# S7DG2_MCU_only_edge_Power_SPI.net
KiCad netlist of a schematic drawn in EAGLE
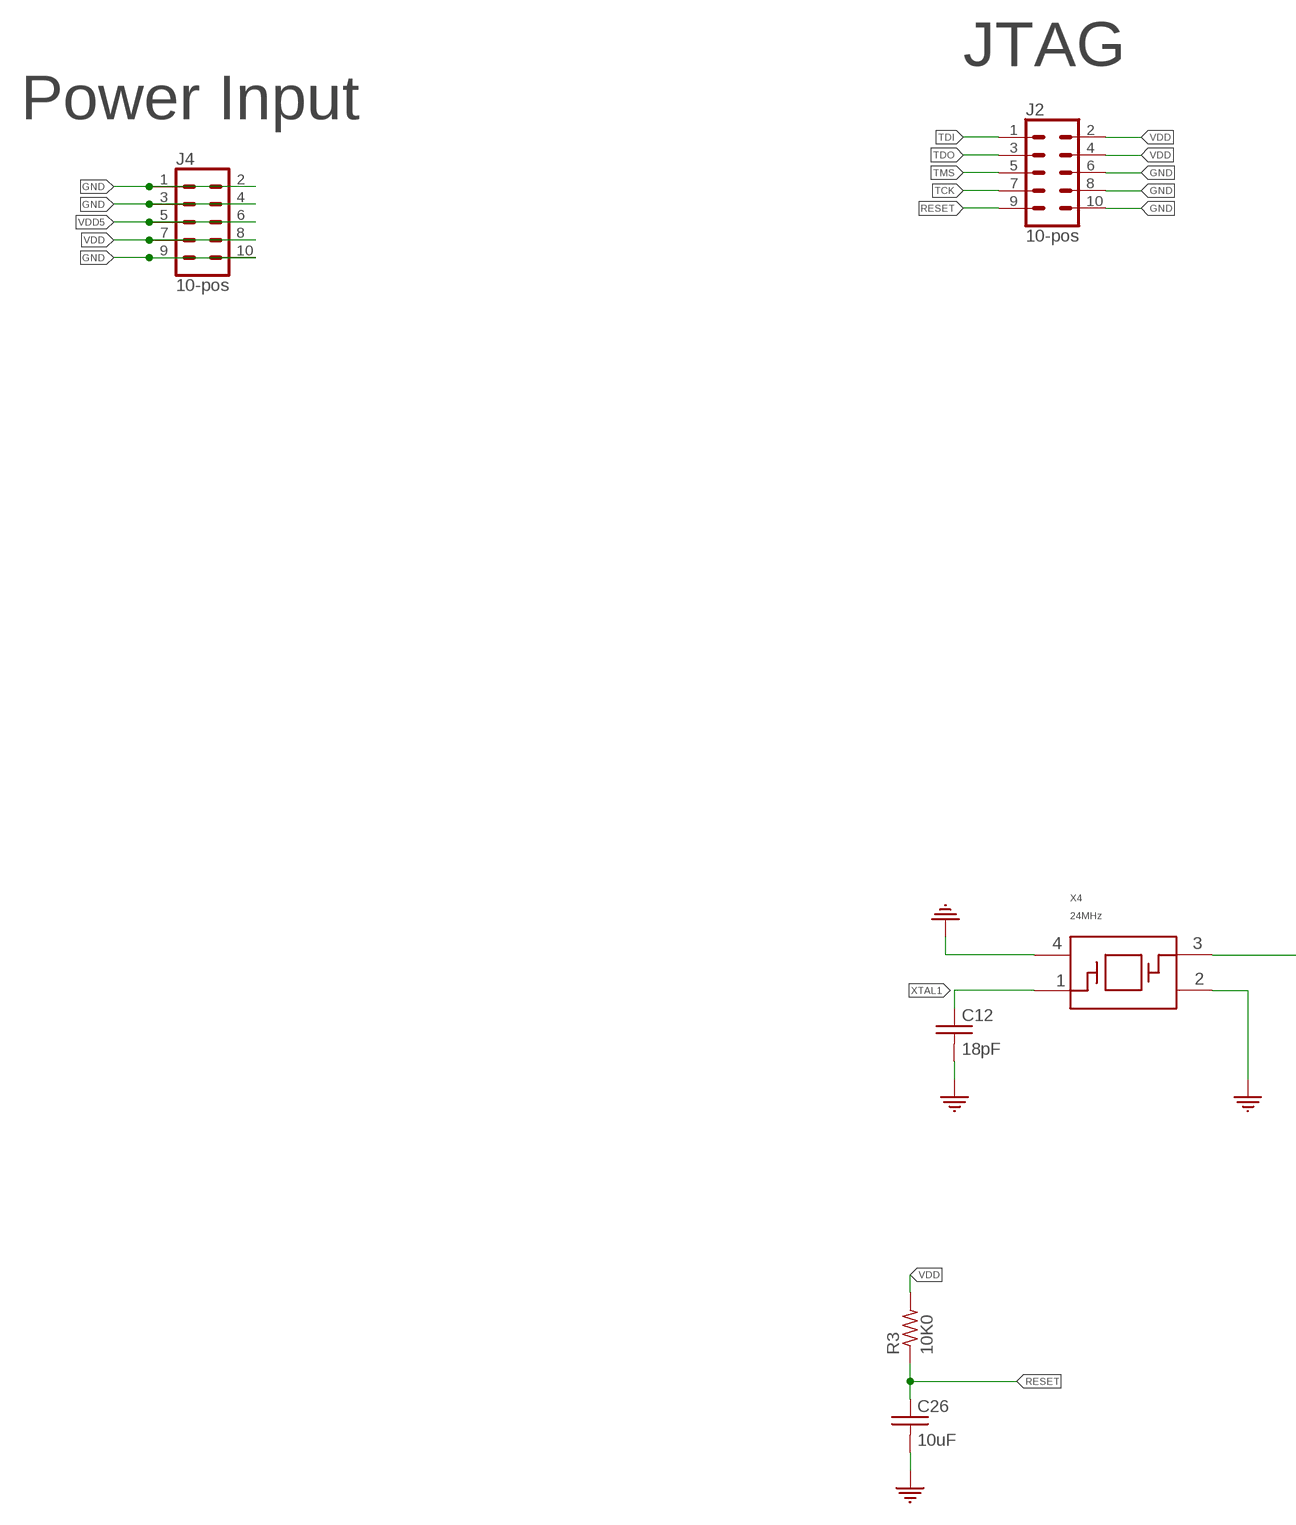
[diagram p0: schematic, sheet 1, part 1 of 2]
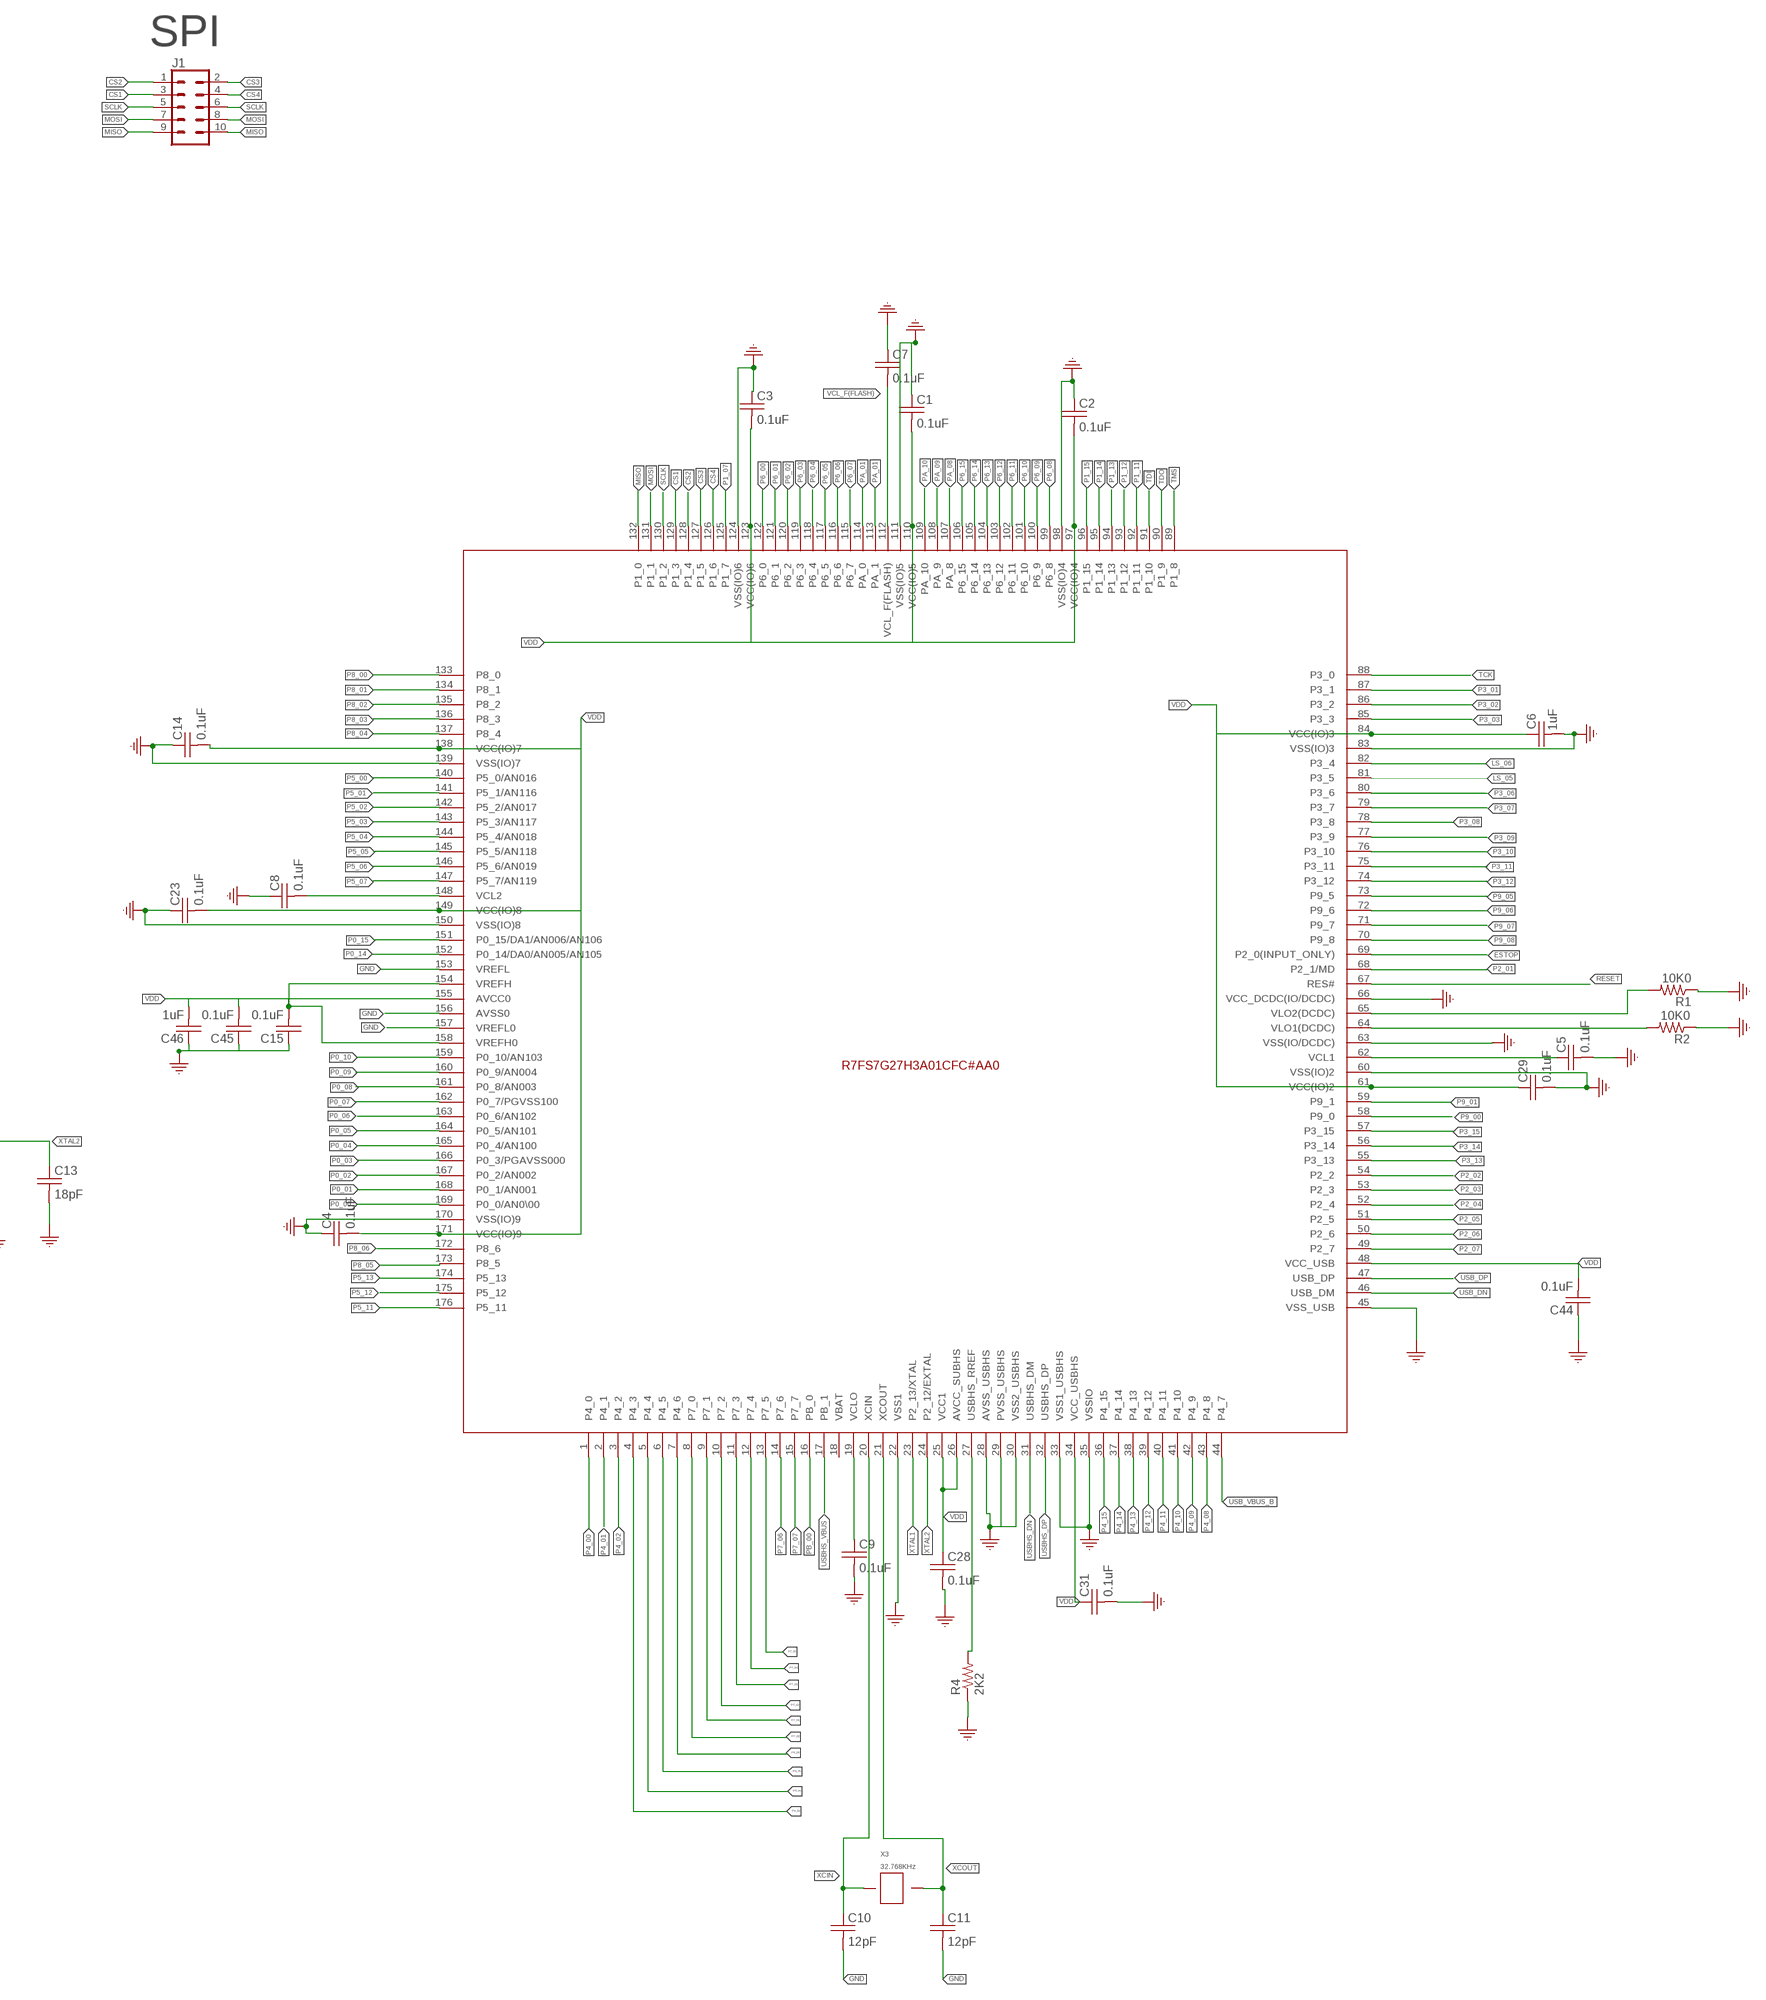
[diagram p1: schematic, sheet 1, part 2 of 2]

(export (version "E")
  (design (tool "Eeschema 10.0.6"))
  (components
    (comp (ref "C1")
      (value "0.1uF")
      (footprint "eagle-import:0402")
      (fields (field (name "PARTNO") "CL05F104ZO5NNNC"))
      (libsource (lib "eagle-import") (part "C_0402_0.1UF"))
    )
    (comp (ref "C2")
      (value "0.1uF")
      (footprint "eagle-import:0402")
      (fields (field (name "PARTNO") "CL05F104ZO5NNNC"))
      (libsource (lib "eagle-import") (part "C_0402_0.1UF"))
    )
    (comp (ref "C3")
      (value "0.1uF")
      (footprint "eagle-import:0402")
      (fields (field (name "PARTNO") "CL05F104ZO5NNNC"))
      (libsource (lib "eagle-import") (part "C_0402_0.1UF"))
    )
    (comp (ref "C4")
      (value "0.1uF")
      (footprint "eagle-import:0402")
      (fields (field (name "PARTNO") "CL05F104ZO5NNNC"))
      (libsource (lib "eagle-import") (part "C_0402_0.1UF"))
    )
    (comp (ref "C5")
      (value "0.1uF")
      (footprint "eagle-import:0402")
      (fields (field (name "PARTNO") "CL05F104ZO5NNNC"))
      (libsource (lib "eagle-import") (part "C_0402_0.1UF"))
    )
    (comp (ref "C6")
      (value "1uF")
      (footprint "eagle-import:0402")
      (fields (field (name "PARTNO") "CL05A105KO5NNNC"))
      (libsource (lib "eagle-import") (part "C_0402_1UF"))
    )
    (comp (ref "C7")
      (value "0.1uF")
      (footprint "eagle-import:0402")
      (fields (field (name "PARTNO") "CL05F104ZO5NNNC"))
      (libsource (lib "eagle-import") (part "C_0402_0.1UF"))
    )
    (comp (ref "C8")
      (value "0.1uF")
      (footprint "eagle-import:0402")
      (fields (field (name "PARTNO") "CL05F104ZO5NNNC"))
      (libsource (lib "eagle-import") (part "C_0402_0.1UF"))
    )
    (comp (ref "C9")
      (value "0.1uF")
      (footprint "eagle-import:0402")
      (fields (field (name "PARTNO") "CL05F104ZO5NNNC"))
      (libsource (lib "eagle-import") (part "C_0402_0.1UF"))
    )
    (comp (ref "C10")
      (value "12pF")
      (footprint "eagle-import:0402")
      (fields (field (name "PARTNO") "CL05C120JB5NNNC"))
      (libsource (lib "eagle-import") (part "C_0402_12PF"))
    )
    (comp (ref "C11")
      (value "12pF")
      (footprint "eagle-import:0402")
      (fields (field (name "PARTNO") "CL05C120JB5NNNC"))
      (libsource (lib "eagle-import") (part "C_0402_12PF"))
    )
    (comp (ref "C12")
      (value "18pF")
      (footprint "eagle-import:0402")
      (fields (field (name "PARTNO") "UMK105CG180JV-F"))
      (libsource (lib "eagle-import") (part "C_0402_18PF"))
    )
    (comp (ref "C13")
      (value "18pF")
      (footprint "eagle-import:0402")
      (fields (field (name "PARTNO") "UMK105CG180JV-F"))
      (libsource (lib "eagle-import") (part "C_0402_18PF"))
    )
    (comp (ref "C14")
      (value "0.1uF")
      (footprint "eagle-import:0402")
      (fields (field (name "PARTNO") "CL05F104ZO5NNNC"))
      (libsource (lib "eagle-import") (part "C_0402_0.1UF"))
    )
    (comp (ref "C15")
      (value "0.1uF")
      (footprint "eagle-import:0402")
      (fields (field (name "PARTNO") "CL05F104ZO5NNNC"))
      (libsource (lib "eagle-import") (part "C_0402_0.1UF"))
    )
    (comp (ref "C23")
      (value "0.1uF")
      (footprint "eagle-import:0402")
      (fields (field (name "PARTNO") "CL05F104ZO5NNNC"))
      (libsource (lib "eagle-import") (part "C_0402_0.1UF"))
    )
    (comp (ref "C26")
      (value "10uF")
      (footprint "eagle-import:0402")
      (fields (field (name "PARTNO") "CL05A106MP8NUB8"))
      (libsource (lib "eagle-import") (part "C_0402_10UF"))
    )
    (comp (ref "C28")
      (value "0.1uF")
      (footprint "eagle-import:0402")
      (fields (field (name "PARTNO") "CL05F104ZO5NNNC"))
      (libsource (lib "eagle-import") (part "C_0402_0.1UF"))
    )
    (comp (ref "C29")
      (value "0.1uF")
      (footprint "eagle-import:0402")
      (fields (field (name "PARTNO") "CL05F104ZO5NNNC"))
      (libsource (lib "eagle-import") (part "C_0402_0.1UF"))
    )
    (comp (ref "C31")
      (value "0.1uF")
      (footprint "eagle-import:0402")
      (fields (field (name "PARTNO") "CL05F104ZO5NNNC"))
      (libsource (lib "eagle-import") (part "C_0402_0.1UF"))
    )
    (comp (ref "C44")
      (value "0.1uF")
      (footprint "eagle-import:0402")
      (fields (field (name "PARTNO") "CL05F104ZO5NNNC"))
      (libsource (lib "eagle-import") (part "C_0402_0.1UF"))
    )
    (comp (ref "C45")
      (value "0.1uF")
      (footprint "eagle-import:0402")
      (fields (field (name "PARTNO") "CL05F104ZO5NNNC"))
      (libsource (lib "eagle-import") (part "C_0402_0.1UF"))
    )
    (comp (ref "C46")
      (value "1uF")
      (footprint "eagle-import:0402")
      (fields (field (name "PARTNO") "CL05A105KO5NNNC"))
      (libsource (lib "eagle-import") (part "C_0402_1UF"))
    )
    (comp (ref "J1")
      (value "CONN_05X2PTH")
      (footprint "eagle-import:2X5")
      (libsource (lib "eagle-import") (part "CONN_05X2PTH"))
    )
    (comp (ref "J2")
      (value "10-pos")
      (footprint "eagle-import:2X5")
      (fields (field (name "PARTNO") "PH2RA-10-UA"))
      (libsource (lib "eagle-import") (part "CONN_05X2_RAPTH"))
    )
    (comp (ref "J4")
      (value "10-pos")
      (footprint "eagle-import:2X5")
      (fields (field (name "PARTNO") "PH2RA-10-UA"))
      (libsource (lib "eagle-import") (part "CONN_05X2_RAPTH"))
    )
    (comp (ref "R1")
      (value "10K0")
      (footprint "eagle-import:0402")
      (fields (field (name "PARTNO") "RMCF0402JT10K0"))
      (libsource (lib "eagle-import") (part "R_0402_10K0"))
    )
    (comp (ref "R2")
      (value "10K0")
      (footprint "eagle-import:0402")
      (fields (field (name "PARTNO") "RMCF0402JT10K0"))
      (libsource (lib "eagle-import") (part "R_0402_10K0"))
    )
    (comp (ref "R3")
      (value "10K0")
      (footprint "eagle-import:0402")
      (fields (field (name "PARTNO") "RMCF0402JT10K0"))
      (libsource (lib "eagle-import") (part "R_0402_10K0"))
    )
    (comp (ref "R4")
      (value "2K2")
      (footprint "eagle-import:0402")
      (fields (field (name "PARTNO") "RMCF0402JT2K20"))
      (libsource (lib "eagle-import") (part "R_0402_2K2"))
    )
    (comp (ref "U2")
      (value "S7G2LQFP176")
      (footprint "eagle-import:LQFP176_24X24")
      (fields (field (name "PARTNO") "R7FS7G27H3A01CFC#AA0"))
      (libsource (lib "eagle-import") (part "RENESAS_S7G2_X_176"))
    )
    (comp (ref "X3")
      (value "32.768KHz")
      (footprint "eagle-import:SMD_X_2_PADS")
      (fields (field (name "PARTNO") "ABS07-32.768KHZ-T"))
      (libsource (lib "eagle-import") (part "XTAL_32.768KHZ"))
    )
    (comp (ref "X4")
      (value "24MHz")
      (footprint "eagle-import:SMD_3225")
      (fields (field (name "PARTNO") "FA-238 24.0000MB-C3 "))
      (libsource (lib "eagle-import") (part "XTAL_24_MHZ"))
    )
  )
  (nets
    (net (code "1") (name "CS1") (class "Default")
      (node (ref "J1") (pin "3") (pinfunction "3_3") (pintype "passive"))
      (node (ref "U2") (pin "129") (pinfunction "P1_3_129") (pintype "bidirectional"))
    )
    (net (code "2") (name "CS2") (class "Default")
      (node (ref "J1") (pin "1") (pinfunction "1_1") (pintype "passive"))
      (node (ref "U2") (pin "128") (pinfunction "P1_4_128") (pintype "bidirectional"))
    )
    (net (code "3") (name "CS3") (class "Default")
      (node (ref "J1") (pin "2") (pinfunction "2_2") (pintype "passive"))
      (node (ref "U2") (pin "127") (pinfunction "P1_5_127") (pintype "bidirectional"))
    )
    (net (code "4") (name "CS4") (class "Default")
      (node (ref "J1") (pin "4") (pinfunction "4_4") (pintype "passive"))
      (node (ref "U2") (pin "126") (pinfunction "P1_6_126") (pintype "bidirectional"))
    )
    (net (code "5") (name "ESTOP") (class "Default")
      (node (ref "U2") (pin "69") (pinfunction "P2_0(INPUT_ONLY)_69") (pintype "bidirectional"))
    )
    (net (code "6") (name "GND") (class "Default")
      (node (ref "C1") (pin "P$1") (pinfunction "1_P$1") (pintype "passive"))
      (node (ref "C10") (pin "P$2") (pinfunction "2_P$2") (pintype "passive"))
      (node (ref "C11") (pin "P$2") (pinfunction "2_P$2") (pintype "passive"))
      (node (ref "C12") (pin "P$2") (pinfunction "2_P$2") (pintype "passive"))
      (node (ref "C13") (pin "P$2") (pinfunction "2_P$2") (pintype "passive"))
      (node (ref "C14") (pin "P$1") (pinfunction "1_P$1") (pintype "passive"))
      (node (ref "C15") (pin "P$1") (pinfunction "1_P$1") (pintype "passive"))
      (node (ref "C2") (pin "P$1") (pinfunction "1_P$1") (pintype "passive"))
      (node (ref "C23") (pin "P$1") (pinfunction "1_P$1") (pintype "passive"))
      (node (ref "C26") (pin "P$2") (pinfunction "2_P$2") (pintype "passive"))
      (node (ref "C28") (pin "P$2") (pinfunction "2_P$2") (pintype "passive"))
      (node (ref "C29") (pin "P$2") (pinfunction "2_P$2") (pintype "passive"))
      (node (ref "C3") (pin "P$1") (pinfunction "1_P$1") (pintype "passive"))
      (node (ref "C31") (pin "P$2") (pinfunction "2_P$2") (pintype "passive"))
      (node (ref "C4") (pin "P$1") (pinfunction "1_P$1") (pintype "passive"))
      (node (ref "C44") (pin "P$1") (pinfunction "1_P$1") (pintype "passive"))
      (node (ref "C45") (pin "P$1") (pinfunction "1_P$1") (pintype "passive"))
      (node (ref "C46") (pin "P$1") (pinfunction "1_P$1") (pintype "passive"))
      (node (ref "C5") (pin "P$2") (pinfunction "2_P$2") (pintype "passive"))
      (node (ref "C6") (pin "P$2") (pinfunction "2_P$2") (pintype "passive"))
      (node (ref "C7") (pin "P$1") (pinfunction "1_P$1") (pintype "passive"))
      (node (ref "C8") (pin "P$1") (pinfunction "1_P$1") (pintype "passive"))
      (node (ref "C9") (pin "P$2") (pinfunction "2_P$2") (pintype "passive"))
      (node (ref "J2") (pin "10") (pinfunction "10_10") (pintype "passive"))
      (node (ref "J2") (pin "6") (pinfunction "6_6") (pintype "passive"))
      (node (ref "J2") (pin "8") (pinfunction "8_8") (pintype "passive"))
      (node (ref "J4") (pin "1") (pinfunction "1_1") (pintype "passive"))
      (node (ref "J4") (pin "10") (pinfunction "10_10") (pintype "passive"))
      (node (ref "J4") (pin "2") (pinfunction "2_2") (pintype "passive"))
      (node (ref "J4") (pin "3") (pinfunction "3_3") (pintype "passive"))
      (node (ref "J4") (pin "4") (pinfunction "4_4") (pintype "passive"))
      (node (ref "J4") (pin "9") (pinfunction "9_9") (pintype "passive"))
      (node (ref "R1") (pin "P$1") (pinfunction "1_P$1") (pintype "passive"))
      (node (ref "R2") (pin "P$1") (pinfunction "1_P$1") (pintype "passive"))
      (node (ref "R4") (pin "P$1") (pinfunction "1_P$1") (pintype "passive"))
      (node (ref "U2") (pin "111") (pinfunction "VSS(IO)5_111") (pintype "bidirectional"))
      (node (ref "U2") (pin "124") (pinfunction "VSS(IO)6_124") (pintype "bidirectional"))
      (node (ref "U2") (pin "139") (pinfunction "VSS(IO)7_139") (pintype "bidirectional"))
      (node (ref "U2") (pin "150") (pinfunction "VSS(IO)8_150") (pintype "bidirectional"))
      (node (ref "U2") (pin "153") (pinfunction "VREFL_153") (pintype "bidirectional"))
      (node (ref "U2") (pin "156") (pinfunction "AVSS0_156") (pintype "bidirectional"))
      (node (ref "U2") (pin "157") (pinfunction "VREFL0_157") (pintype "bidirectional"))
      (node (ref "U2") (pin "170") (pinfunction "VSS(IO)9_170") (pintype "bidirectional"))
      (node (ref "U2") (pin "22") (pinfunction "VSS1_22") (pintype "bidirectional"))
      (node (ref "U2") (pin "28") (pinfunction "AVSS_USBHS_28") (pintype "bidirectional"))
      (node (ref "U2") (pin "29") (pinfunction "PVSS_USBHS_29") (pintype "bidirectional"))
      (node (ref "U2") (pin "30") (pinfunction "VSS2_USBHS_30") (pintype "bidirectional"))
      (node (ref "U2") (pin "33") (pinfunction "VSS1_USBHS_33") (pintype "bidirectional"))
      (node (ref "U2") (pin "35") (pinfunction "VSSIO_35") (pintype "bidirectional"))
      (node (ref "U2") (pin "45") (pinfunction "VSS_USB_45") (pintype "bidirectional"))
      (node (ref "U2") (pin "60") (pinfunction "VSS(IO)2_60") (pintype "bidirectional"))
      (node (ref "U2") (pin "63") (pinfunction "VSS(IO/DCDC)_63") (pintype "bidirectional"))
      (node (ref "U2") (pin "66") (pinfunction "VCC_DCDC(IO/DCDC)_66") (pintype "bidirectional"))
      (node (ref "U2") (pin "83") (pinfunction "VSS(IO)3_83") (pintype "bidirectional"))
      (node (ref "U2") (pin "98") (pinfunction "VSS(IO)4_98") (pintype "bidirectional"))
      (node (ref "X4") (pin "2") (pinfunction "2_2") (pintype "bidirectional"))
      (node (ref "X4") (pin "4") (pinfunction "4_4") (pintype "bidirectional"))
    )
    (net (code "7") (name "LS_05") (class "Default")
      (node (ref "U2") (pin "81") (pinfunction "P3_5_81") (pintype "bidirectional"))
    )
    (net (code "8") (name "LS_06") (class "Default")
      (node (ref "U2") (pin "82") (pinfunction "P3_4_82") (pintype "bidirectional"))
    )
    (net (code "9") (name "MISO") (class "Default")
      (node (ref "J1") (pin "10") (pinfunction "10_10") (pintype "passive"))
      (node (ref "J1") (pin "9") (pinfunction "9_9") (pintype "passive"))
      (node (ref "U2") (pin "132") (pinfunction "P1_0_132") (pintype "bidirectional"))
    )
    (net (code "10") (name "MOSI") (class "Default")
      (node (ref "J1") (pin "7") (pinfunction "7_7") (pintype "passive"))
      (node (ref "J1") (pin "8") (pinfunction "8_8") (pintype "passive"))
      (node (ref "U2") (pin "131") (pinfunction "P1_1_131") (pintype "bidirectional"))
    )
    (net (code "11") (name "Net-(C5-1)") (class "Default")
      (node (ref "C5") (pin "P$1") (pinfunction "1_P$1") (pintype "passive"))
      (node (ref "U2") (pin "62") (pinfunction "VCL1_62") (pintype "bidirectional"))
    )
    (net (code "12") (name "Net-(C8-2)") (class "Default")
      (node (ref "C8") (pin "P$2") (pinfunction "2_P$2") (pintype "passive"))
      (node (ref "U2") (pin "148") (pinfunction "VCL2_148") (pintype "bidirectional"))
    )
    (net (code "13") (name "Net-(C9-1)") (class "Default")
      (node (ref "C9") (pin "P$1") (pinfunction "1_P$1") (pintype "passive"))
      (node (ref "U2") (pin "19") (pinfunction "VCLO_19") (pintype "bidirectional"))
    )
    (net (code "14") (name "Net-(R1-2)") (class "Default")
      (node (ref "R1") (pin "P$2") (pinfunction "2_P$2") (pintype "passive"))
      (node (ref "U2") (pin "65") (pinfunction "VLO2(DCDC)_65") (pintype "bidirectional"))
    )
    (net (code "15") (name "Net-(R2-2)") (class "Default")
      (node (ref "R2") (pin "P$2") (pinfunction "2_P$2") (pintype "passive"))
      (node (ref "U2") (pin "64") (pinfunction "VLO1(DCDC)_64") (pintype "bidirectional"))
    )
    (net (code "16") (name "Net-(R4-2)") (class "Default")
      (node (ref "R4") (pin "P$2") (pinfunction "2_P$2") (pintype "passive"))
      (node (ref "U2") (pin "27") (pinfunction "USBHS_RREF_27") (pintype "bidirectional"))
    )
    (net (code "17") (name "P0_00") (class "Default")
      (node (ref "U2") (pin "169") (pinfunction "P0_0/AN0\\00_169") (pintype "bidirectional"))
    )
    (net (code "18") (name "P0_01") (class "Default")
      (node (ref "U2") (pin "168") (pinfunction "P0_1/AN001_168") (pintype "bidirectional"))
    )
    (net (code "19") (name "P0_02") (class "Default")
      (node (ref "U2") (pin "167") (pinfunction "P0_2/AN002_167") (pintype "bidirectional"))
    )
    (net (code "20") (name "P0_03") (class "Default")
      (node (ref "U2") (pin "166") (pinfunction "P0_3/PGAVSS000_166") (pintype "bidirectional"))
    )
    (net (code "21") (name "P0_04") (class "Default")
      (node (ref "U2") (pin "165") (pinfunction "P0_4/AN100_165") (pintype "bidirectional"))
    )
    (net (code "22") (name "P0_05") (class "Default")
      (node (ref "U2") (pin "164") (pinfunction "P0_5/AN101_164") (pintype "bidirectional"))
    )
    (net (code "23") (name "P0_06") (class "Default")
      (node (ref "U2") (pin "163") (pinfunction "P0_6/AN102_163") (pintype "bidirectional"))
    )
    (net (code "24") (name "P0_07") (class "Default")
      (node (ref "U2") (pin "162") (pinfunction "P0_7/PGVSS100_162") (pintype "bidirectional"))
    )
    (net (code "25") (name "P0_08") (class "Default")
      (node (ref "U2") (pin "161") (pinfunction "P0_8/AN003_161") (pintype "bidirectional"))
    )
    (net (code "26") (name "P0_09") (class "Default")
      (node (ref "U2") (pin "160") (pinfunction "P0_9/AN004_160") (pintype "bidirectional"))
    )
    (net (code "27") (name "P0_10") (class "Default")
      (node (ref "U2") (pin "159") (pinfunction "P0_10/AN103_159") (pintype "bidirectional"))
    )
    (net (code "28") (name "P0_14") (class "Default")
      (node (ref "U2") (pin "152") (pinfunction "P0_14/DA0/AN005/AN105_152") (pintype "bidirectional"))
    )
    (net (code "29") (name "P0_15") (class "Default")
      (node (ref "U2") (pin "151") (pinfunction "P0_15/DA1/AN006/AN106_151") (pintype "bidirectional"))
    )
    (net (code "30") (name "P1_07") (class "Default")
      (node (ref "U2") (pin "125") (pinfunction "P1_7_125") (pintype "bidirectional"))
    )
    (net (code "31") (name "P1_11") (class "Default")
      (node (ref "U2") (pin "92") (pinfunction "P1_11_92") (pintype "bidirectional"))
    )
    (net (code "32") (name "P1_12") (class "Default")
      (node (ref "U2") (pin "93") (pinfunction "P1_12_93") (pintype "bidirectional"))
    )
    (net (code "33") (name "P1_13") (class "Default")
      (node (ref "U2") (pin "94") (pinfunction "P1_13_94") (pintype "bidirectional"))
    )
    (net (code "34") (name "P1_14") (class "Default")
      (node (ref "U2") (pin "95") (pinfunction "P1_14_95") (pintype "bidirectional"))
    )
    (net (code "35") (name "P1_15") (class "Default")
      (node (ref "U2") (pin "96") (pinfunction "P1_15_96") (pintype "bidirectional"))
    )
    (net (code "36") (name "P2_01") (class "Default")
      (node (ref "U2") (pin "68") (pinfunction "P2_1/MD_68") (pintype "bidirectional"))
    )
    (net (code "37") (name "P2_02") (class "Default")
      (node (ref "U2") (pin "54") (pinfunction "P2_2_54") (pintype "bidirectional"))
    )
    (net (code "38") (name "P2_03") (class "Default")
      (node (ref "U2") (pin "53") (pinfunction "P2_3_53") (pintype "bidirectional"))
    )
    (net (code "39") (name "P2_04") (class "Default")
      (node (ref "U2") (pin "52") (pinfunction "P2_4_52") (pintype "bidirectional"))
    )
    (net (code "40") (name "P2_05") (class "Default")
      (node (ref "U2") (pin "51") (pinfunction "P2_5_51") (pintype "bidirectional"))
    )
    (net (code "41") (name "P2_06") (class "Default")
      (node (ref "U2") (pin "50") (pinfunction "P2_6_50") (pintype "bidirectional"))
    )
    (net (code "42") (name "P2_07") (class "Default")
      (node (ref "U2") (pin "49") (pinfunction "P2_7_49") (pintype "bidirectional"))
    )
    (net (code "43") (name "P3_01") (class "Default")
      (node (ref "U2") (pin "87") (pinfunction "P3_1_87") (pintype "bidirectional"))
    )
    (net (code "44") (name "P3_02") (class "Default")
      (node (ref "U2") (pin "86") (pinfunction "P3_2_86") (pintype "bidirectional"))
    )
    (net (code "45") (name "P3_03") (class "Default")
      (node (ref "U2") (pin "85") (pinfunction "P3_3_85") (pintype "bidirectional"))
    )
    (net (code "46") (name "P3_06") (class "Default")
      (node (ref "U2") (pin "80") (pinfunction "P3_6_80") (pintype "bidirectional"))
    )
    (net (code "47") (name "P3_07") (class "Default")
      (node (ref "U2") (pin "79") (pinfunction "P3_7_79") (pintype "bidirectional"))
    )
    (net (code "48") (name "P3_08") (class "Default")
      (node (ref "U2") (pin "78") (pinfunction "P3_8_78") (pintype "bidirectional"))
    )
    (net (code "49") (name "P3_09") (class "Default")
      (node (ref "U2") (pin "77") (pinfunction "P3_9_77") (pintype "bidirectional"))
    )
    (net (code "50") (name "P3_10") (class "Default")
      (node (ref "U2") (pin "76") (pinfunction "P3_10_76") (pintype "bidirectional"))
    )
    (net (code "51") (name "P3_11") (class "Default")
      (node (ref "U2") (pin "75") (pinfunction "P3_11_75") (pintype "bidirectional"))
    )
    (net (code "52") (name "P3_12") (class "Default")
      (node (ref "U2") (pin "74") (pinfunction "P3_12_74") (pintype "bidirectional"))
    )
    (net (code "53") (name "P3_13") (class "Default")
      (node (ref "U2") (pin "55") (pinfunction "P3_13_55") (pintype "bidirectional"))
    )
    (net (code "54") (name "P3_14") (class "Default")
      (node (ref "U2") (pin "56") (pinfunction "P3_14_56") (pintype "bidirectional"))
    )
    (net (code "55") (name "P3_15") (class "Default")
      (node (ref "U2") (pin "57") (pinfunction "P3_15_57") (pintype "bidirectional"))
    )
    (net (code "56") (name "P4_00") (class "Default")
      (node (ref "U2") (pin "1") (pinfunction "P4_0_1") (pintype "bidirectional"))
    )
    (net (code "57") (name "P4_01") (class "Default")
      (node (ref "U2") (pin "2") (pinfunction "P4_1_2") (pintype "bidirectional"))
    )
    (net (code "58") (name "P4_02") (class "Default")
      (node (ref "U2") (pin "3") (pinfunction "P4_2_3") (pintype "bidirectional"))
    )
    (net (code "59") (name "P4_03") (class "Default")
      (node (ref "U2") (pin "4") (pinfunction "P4_3_4") (pintype "bidirectional"))
    )
    (net (code "60") (name "P4_04") (class "Default")
      (node (ref "U2") (pin "5") (pinfunction "P4_4_5") (pintype "bidirectional"))
    )
    (net (code "61") (name "P4_05") (class "Default")
      (node (ref "U2") (pin "6") (pinfunction "P4_5_6") (pintype "bidirectional"))
    )
    (net (code "62") (name "P4_06") (class "Default")
      (node (ref "U2") (pin "7") (pinfunction "P4_6_7") (pintype "bidirectional"))
    )
    (net (code "63") (name "P4_08") (class "Default")
      (node (ref "U2") (pin "43") (pinfunction "P4_8_43") (pintype "bidirectional"))
    )
    (net (code "64") (name "P4_09") (class "Default")
      (node (ref "U2") (pin "42") (pinfunction "P4_9_42") (pintype "bidirectional"))
    )
    (net (code "65") (name "P4_10") (class "Default")
      (node (ref "U2") (pin "41") (pinfunction "P4_10_41") (pintype "bidirectional"))
    )
    (net (code "66") (name "P4_11") (class "Default")
      (node (ref "U2") (pin "40") (pinfunction "P4_11_40") (pintype "bidirectional"))
    )
    (net (code "67") (name "P4_12") (class "Default")
      (node (ref "U2") (pin "39") (pinfunction "P4_12_39") (pintype "bidirectional"))
    )
    (net (code "68") (name "P4_13") (class "Default")
      (node (ref "U2") (pin "38") (pinfunction "P4_13_38") (pintype "bidirectional"))
    )
    (net (code "69") (name "P4_14") (class "Default")
      (node (ref "U2") (pin "37") (pinfunction "P4_14_37") (pintype "bidirectional"))
    )
    (net (code "70") (name "P4_15") (class "Default")
      (node (ref "U2") (pin "36") (pinfunction "P4_15_36") (pintype "bidirectional"))
    )
    (net (code "71") (name "P5_00") (class "Default")
      (node (ref "U2") (pin "140") (pinfunction "P5_0/AN016_140") (pintype "bidirectional"))
    )
    (net (code "72") (name "P5_01") (class "Default")
      (node (ref "U2") (pin "141") (pinfunction "P5_1/AN116_141") (pintype "bidirectional"))
    )
    (net (code "73") (name "P5_02") (class "Default")
      (node (ref "U2") (pin "142") (pinfunction "P5_2/AN017_142") (pintype "bidirectional"))
    )
    (net (code "74") (name "P5_03") (class "Default")
      (node (ref "U2") (pin "143") (pinfunction "P5_3/AN117_143") (pintype "bidirectional"))
    )
    (net (code "75") (name "P5_04") (class "Default")
      (node (ref "U2") (pin "144") (pinfunction "P5_4/AN018_144") (pintype "bidirectional"))
    )
    (net (code "76") (name "P5_05") (class "Default")
      (node (ref "U2") (pin "145") (pinfunction "P5_5/AN118_145") (pintype "bidirectional"))
    )
    (net (code "77") (name "P5_06") (class "Default")
      (node (ref "U2") (pin "146") (pinfunction "P5_6/AN019_146") (pintype "bidirectional"))
    )
    (net (code "78") (name "P5_07") (class "Default")
      (node (ref "U2") (pin "147") (pinfunction "P5_7/AN119_147") (pintype "bidirectional"))
    )
    (net (code "79") (name "P5_11") (class "Default")
      (node (ref "U2") (pin "176") (pinfunction "P5_11_176") (pintype "bidirectional"))
    )
    (net (code "80") (name "P5_12") (class "Default")
      (node (ref "U2") (pin "175") (pinfunction "P5_12_175") (pintype "bidirectional"))
    )
    (net (code "81") (name "P5_13") (class "Default")
      (node (ref "U2") (pin "174") (pinfunction "P5_13_174") (pintype "bidirectional"))
    )
    (net (code "82") (name "P6_00") (class "Default")
      (node (ref "U2") (pin "122") (pinfunction "P6_0_122") (pintype "bidirectional"))
    )
    (net (code "83") (name "P6_01") (class "Default")
      (node (ref "U2") (pin "121") (pinfunction "P6_1_121") (pintype "bidirectional"))
    )
    (net (code "84") (name "P6_02") (class "Default")
      (node (ref "U2") (pin "120") (pinfunction "P6_2_120") (pintype "bidirectional"))
    )
    (net (code "85") (name "P6_03") (class "Default")
      (node (ref "U2") (pin "119") (pinfunction "P6_3_119") (pintype "bidirectional"))
    )
    (net (code "86") (name "P6_04") (class "Default")
      (node (ref "U2") (pin "118") (pinfunction "P6_4_118") (pintype "bidirectional"))
    )
    (net (code "87") (name "P6_05") (class "Default")
      (node (ref "U2") (pin "117") (pinfunction "P6_5_117") (pintype "bidirectional"))
    )
    (net (code "88") (name "P6_06") (class "Default")
      (node (ref "U2") (pin "116") (pinfunction "P6_6_116") (pintype "bidirectional"))
    )
    (net (code "89") (name "P6_07") (class "Default")
      (node (ref "U2") (pin "115") (pinfunction "P6_7_115") (pintype "bidirectional"))
    )
    (net (code "90") (name "P6_08") (class "Default")
      (node (ref "U2") (pin "99") (pinfunction "P6_8_99") (pintype "bidirectional"))
    )
    (net (code "91") (name "P6_09") (class "Default")
      (node (ref "U2") (pin "100") (pinfunction "P6_9_100") (pintype "bidirectional"))
    )
    (net (code "92") (name "P6_10") (class "Default")
      (node (ref "U2") (pin "101") (pinfunction "P6_10_101") (pintype "bidirectional"))
    )
    (net (code "93") (name "P6_11") (class "Default")
      (node (ref "U2") (pin "102") (pinfunction "P6_11_102") (pintype "bidirectional"))
    )
    (net (code "94") (name "P6_12") (class "Default")
      (node (ref "U2") (pin "103") (pinfunction "P6_12_103") (pintype "bidirectional"))
    )
    (net (code "95") (name "P6_13") (class "Default")
      (node (ref "U2") (pin "104") (pinfunction "P6_13_104") (pintype "bidirectional"))
    )
    (net (code "96") (name "P6_14") (class "Default")
      (node (ref "U2") (pin "105") (pinfunction "P6_14_105") (pintype "bidirectional"))
    )
    (net (code "97") (name "P6_15") (class "Default")
      (node (ref "U2") (pin "106") (pinfunction "P6_15_106") (pintype "bidirectional"))
    )
    (net (code "98") (name "P7_00") (class "Default")
      (node (ref "U2") (pin "8") (pinfunction "P7_0_8") (pintype "bidirectional"))
    )
    (net (code "99") (name "P7_01") (class "Default")
      (node (ref "U2") (pin "9") (pinfunction "P7_1_9") (pintype "bidirectional"))
    )
    (net (code "100") (name "P7_02") (class "Default")
      (node (ref "U2") (pin "10") (pinfunction "P7_2_10") (pintype "bidirectional"))
    )
    (net (code "101") (name "P7_03") (class "Default")
      (node (ref "U2") (pin "11") (pinfunction "P7_3_11") (pintype "bidirectional"))
    )
    (net (code "102") (name "P7_04") (class "Default")
      (node (ref "U2") (pin "12") (pinfunction "P7_4_12") (pintype "bidirectional"))
    )
    (net (code "103") (name "P7_05") (class "Default")
      (node (ref "U2") (pin "13") (pinfunction "P7_5_13") (pintype "bidirectional"))
    )
    (net (code "104") (name "P7_06") (class "Default")
      (node (ref "U2") (pin "14") (pinfunction "P7_6_14") (pintype "bidirectional"))
    )
    (net (code "105") (name "P7_07") (class "Default")
      (node (ref "U2") (pin "15") (pinfunction "P7_7_15") (pintype "bidirectional"))
    )
    (net (code "106") (name "P8_00") (class "Default")
      (node (ref "U2") (pin "133") (pinfunction "P8_0_133") (pintype "bidirectional"))
    )
    (net (code "107") (name "P8_01") (class "Default")
      (node (ref "U2") (pin "134") (pinfunction "P8_1_134") (pintype "bidirectional"))
    )
    (net (code "108") (name "P8_02") (class "Default")
      (node (ref "U2") (pin "135") (pinfunction "P8_2_135") (pintype "bidirectional"))
    )
    (net (code "109") (name "P8_03") (class "Default")
      (node (ref "U2") (pin "136") (pinfunction "P8_3_136") (pintype "bidirectional"))
    )
    (net (code "110") (name "P8_04") (class "Default")
      (node (ref "U2") (pin "137") (pinfunction "P8_4_137") (pintype "bidirectional"))
    )
    (net (code "111") (name "P8_05") (class "Default")
      (node (ref "U2") (pin "173") (pinfunction "P8_5_173") (pintype "bidirectional"))
    )
    (net (code "112") (name "P8_06") (class "Default")
      (node (ref "U2") (pin "172") (pinfunction "P8_6_172") (pintype "bidirectional"))
    )
    (net (code "113") (name "P9_00") (class "Default")
      (node (ref "U2") (pin "58") (pinfunction "P9_0_58") (pintype "bidirectional"))
    )
    (net (code "114") (name "P9_01") (class "Default")
      (node (ref "U2") (pin "59") (pinfunction "P9_1_59") (pintype "bidirectional"))
    )
    (net (code "115") (name "P9_05") (class "Default")
      (node (ref "U2") (pin "73") (pinfunction "P9_5_73") (pintype "bidirectional"))
    )
    (net (code "116") (name "P9_06") (class "Default")
      (node (ref "U2") (pin "72") (pinfunction "P9_6_72") (pintype "bidirectional"))
    )
    (net (code "117") (name "P9_07") (class "Default")
      (node (ref "U2") (pin "71") (pinfunction "P9_7_71") (pintype "bidirectional"))
    )
    (net (code "118") (name "P9_08") (class "Default")
      (node (ref "U2") (pin "70") (pinfunction "P9_8_70") (pintype "bidirectional"))
    )
    (net (code "119") (name "PA_01") (class "Default")
      (node (ref "U2") (pin "113") (pinfunction "PA_1_113") (pintype "bidirectional"))
      (node (ref "U2") (pin "114") (pinfunction "PA_0_114") (pintype "bidirectional"))
    )
    (net (code "120") (name "PA_08") (class "Default")
      (node (ref "U2") (pin "107") (pinfunction "PA_8_107") (pintype "bidirectional"))
    )
    (net (code "121") (name "PA_09") (class "Default")
      (node (ref "U2") (pin "108") (pinfunction "PA_9_108") (pintype "bidirectional"))
    )
    (net (code "122") (name "PA_10") (class "Default")
      (node (ref "U2") (pin "109") (pinfunction "PA_10_109") (pintype "bidirectional"))
    )
    (net (code "123") (name "PB_00") (class "Default")
      (node (ref "U2") (pin "16") (pinfunction "PB_0_16") (pintype "bidirectional"))
    )
    (net (code "124") (name "RESET") (class "Default")
      (node (ref "C26") (pin "P$1") (pinfunction "1_P$1") (pintype "passive"))
      (node (ref "J2") (pin "9") (pinfunction "9_9") (pintype "passive"))
      (node (ref "R3") (pin "P$1") (pinfunction "1_P$1") (pintype "passive"))
      (node (ref "U2") (pin "67") (pinfunction "RES#_67") (pintype "bidirectional"))
    )
    (net (code "125") (name "SCLK") (class "Default")
      (node (ref "J1") (pin "5") (pinfunction "5_5") (pintype "passive"))
      (node (ref "J1") (pin "6") (pinfunction "6_6") (pintype "passive"))
      (node (ref "U2") (pin "130") (pinfunction "P1_2_130") (pintype "bidirectional"))
    )
    (net (code "126") (name "TCK") (class "Default")
      (node (ref "J2") (pin "7") (pinfunction "7_7") (pintype "passive"))
      (node (ref "U2") (pin "88") (pinfunction "P3_0_88") (pintype "bidirectional"))
    )
    (net (code "127") (name "TDI") (class "Default")
      (node (ref "J2") (pin "1") (pinfunction "1_1") (pintype "passive"))
      (node (ref "U2") (pin "91") (pinfunction "P1_10_91") (pintype "bidirectional"))
    )
    (net (code "128") (name "TDO") (class "Default")
      (node (ref "J2") (pin "3") (pinfunction "3_3") (pintype "passive"))
      (node (ref "U2") (pin "90") (pinfunction "P1_9_90") (pintype "bidirectional"))
    )
    (net (code "129") (name "TMS") (class "Default")
      (node (ref "J2") (pin "5") (pinfunction "5_5") (pintype "passive"))
      (node (ref "U2") (pin "89") (pinfunction "P1_8_89") (pintype "bidirectional"))
    )
    (net (code "130") (name "USBHS_DN") (class "Default")
      (node (ref "U2") (pin "31") (pinfunction "USBHS_DM_31") (pintype "bidirectional"))
    )
    (net (code "131") (name "USBHS_DP") (class "Default")
      (node (ref "U2") (pin "32") (pinfunction "USBHS_DP_32") (pintype "bidirectional"))
    )
    (net (code "132") (name "USBHS_VBUS") (class "Default")
      (node (ref "U2") (pin "17") (pinfunction "PB_1_17") (pintype "bidirectional"))
    )
    (net (code "133") (name "USB_DN") (class "Default")
      (node (ref "U2") (pin "46") (pinfunction "USB_DM_46") (pintype "bidirectional"))
    )
    (net (code "134") (name "USB_DP") (class "Default")
      (node (ref "U2") (pin "47") (pinfunction "USB_DP_47") (pintype "bidirectional"))
    )
    (net (code "135") (name "USB_VBUS_B") (class "Default")
      (node (ref "U2") (pin "44") (pinfunction "P4_7_44") (pintype "bidirectional"))
    )
    (net (code "136") (name "VCL_F(FLASH)") (class "Default")
      (node (ref "C7") (pin "P$2") (pinfunction "2_P$2") (pintype "passive"))
      (node (ref "U2") (pin "112") (pinfunction "VCL_F(FLASH)_112") (pintype "bidirectional"))
    )
    (net (code "137") (name "VDD") (class "Default")
      (node (ref "C1") (pin "P$2") (pinfunction "2_P$2") (pintype "passive"))
      (node (ref "C14") (pin "P$2") (pinfunction "2_P$2") (pintype "passive"))
      (node (ref "C15") (pin "P$2") (pinfunction "2_P$2") (pintype "passive"))
      (node (ref "C2") (pin "P$2") (pinfunction "2_P$2") (pintype "passive"))
      (node (ref "C23") (pin "P$2") (pinfunction "2_P$2") (pintype "passive"))
      (node (ref "C28") (pin "P$1") (pinfunction "1_P$1") (pintype "passive"))
      (node (ref "C29") (pin "P$1") (pinfunction "1_P$1") (pintype "passive"))
      (node (ref "C3") (pin "P$2") (pinfunction "2_P$2") (pintype "passive"))
      (node (ref "C31") (pin "P$1") (pinfunction "1_P$1") (pintype "passive"))
      (node (ref "C4") (pin "P$2") (pinfunction "2_P$2") (pintype "passive"))
      (node (ref "C44") (pin "P$2") (pinfunction "2_P$2") (pintype "passive"))
      (node (ref "C45") (pin "P$2") (pinfunction "2_P$2") (pintype "passive"))
      (node (ref "C46") (pin "P$2") (pinfunction "2_P$2") (pintype "passive"))
      (node (ref "C6") (pin "P$1") (pinfunction "1_P$1") (pintype "passive"))
      (node (ref "J2") (pin "2") (pinfunction "2_2") (pintype "passive"))
      (node (ref "J2") (pin "4") (pinfunction "4_4") (pintype "passive"))
      (node (ref "J4") (pin "7") (pinfunction "7_7") (pintype "passive"))
      (node (ref "J4") (pin "8") (pinfunction "8_8") (pintype "passive"))
      (node (ref "R3") (pin "P$2") (pinfunction "2_P$2") (pintype "passive"))
      (node (ref "U2") (pin "110") (pinfunction "VCC(IO)5_110") (pintype "bidirectional"))
      (node (ref "U2") (pin "123") (pinfunction "VCC(IO)6_123") (pintype "bidirectional"))
      (node (ref "U2") (pin "138") (pinfunction "VCC(IO)7_138") (pintype "bidirectional"))
      (node (ref "U2") (pin "149") (pinfunction "VCC(IO)8_149") (pintype "bidirectional"))
      (node (ref "U2") (pin "154") (pinfunction "VREFH_154") (pintype "bidirectional"))
      (node (ref "U2") (pin "155") (pinfunction "AVCC0_155") (pintype "bidirectional"))
      (node (ref "U2") (pin "158") (pinfunction "VREFH0_158") (pintype "bidirectional"))
      (node (ref "U2") (pin "171") (pinfunction "VCC(IO)9_171") (pintype "bidirectional"))
      (node (ref "U2") (pin "25") (pinfunction "VCC1_25") (pintype "bidirectional"))
      (node (ref "U2") (pin "26") (pinfunction "AVCC_SUBHS_26") (pintype "bidirectional"))
      (node (ref "U2") (pin "34") (pinfunction "VCC_USBHS_34") (pintype "bidirectional"))
      (node (ref "U2") (pin "48") (pinfunction "VCC_USB_48") (pintype "bidirectional"))
      (node (ref "U2") (pin "61") (pinfunction "VCC(IO)2_61") (pintype "bidirectional"))
      (node (ref "U2") (pin "84") (pinfunction "VCC(IO)3_84") (pintype "bidirectional"))
      (node (ref "U2") (pin "97") (pinfunction "VCC(IO)4_97") (pintype "bidirectional"))
    )
    (net (code "138") (name "VDD5") (class "Default")
      (node (ref "J4") (pin "5") (pinfunction "5_5") (pintype "passive"))
      (node (ref "J4") (pin "6") (pinfunction "6_6") (pintype "passive"))
    )
    (net (code "139") (name "XCIN") (class "Default")
      (node (ref "C10") (pin "P$1") (pinfunction "1_P$1") (pintype "passive"))
      (node (ref "U2") (pin "20") (pinfunction "XCIN_20") (pintype "bidirectional"))
      (node (ref "X3") (pin "P$1") (pinfunction "P$1_P$1") (pintype "bidirectional"))
    )
    (net (code "140") (name "XCOUT") (class "Default")
      (node (ref "C11") (pin "P$1") (pinfunction "1_P$1") (pintype "passive"))
      (node (ref "U2") (pin "21") (pinfunction "XCOUT_21") (pintype "bidirectional"))
      (node (ref "X3") (pin "P$2") (pinfunction "P$2_P$2") (pintype "bidirectional"))
    )
    (net (code "141") (name "XTAL1") (class "Default")
      (node (ref "C12") (pin "P$1") (pinfunction "1_P$1") (pintype "passive"))
      (node (ref "U2") (pin "23") (pinfunction "P2_13/XTAL_23") (pintype "bidirectional"))
      (node (ref "X4") (pin "1") (pinfunction "1_1") (pintype "bidirectional"))
    )
    (net (code "142") (name "XTAL2") (class "Default")
      (node (ref "C13") (pin "P$1") (pinfunction "1_P$1") (pintype "passive"))
      (node (ref "U2") (pin "24") (pinfunction "P2_12/EXTAL_24") (pintype "bidirectional"))
      (node (ref "X4") (pin "3") (pinfunction "3_3") (pintype "bidirectional"))
    )
    (net (code "143") (name "unconnected-(U2-VBAT-Pad18)") (class "Default")
      (node (ref "U2") (pin "18") (pinfunction "VBAT_18") (pintype "bidirectional"))
    )
  )
)
